# MSP430F5529_Relays_PressureSensor.net
KiCad netlist of a schematic drawn in EAGLE
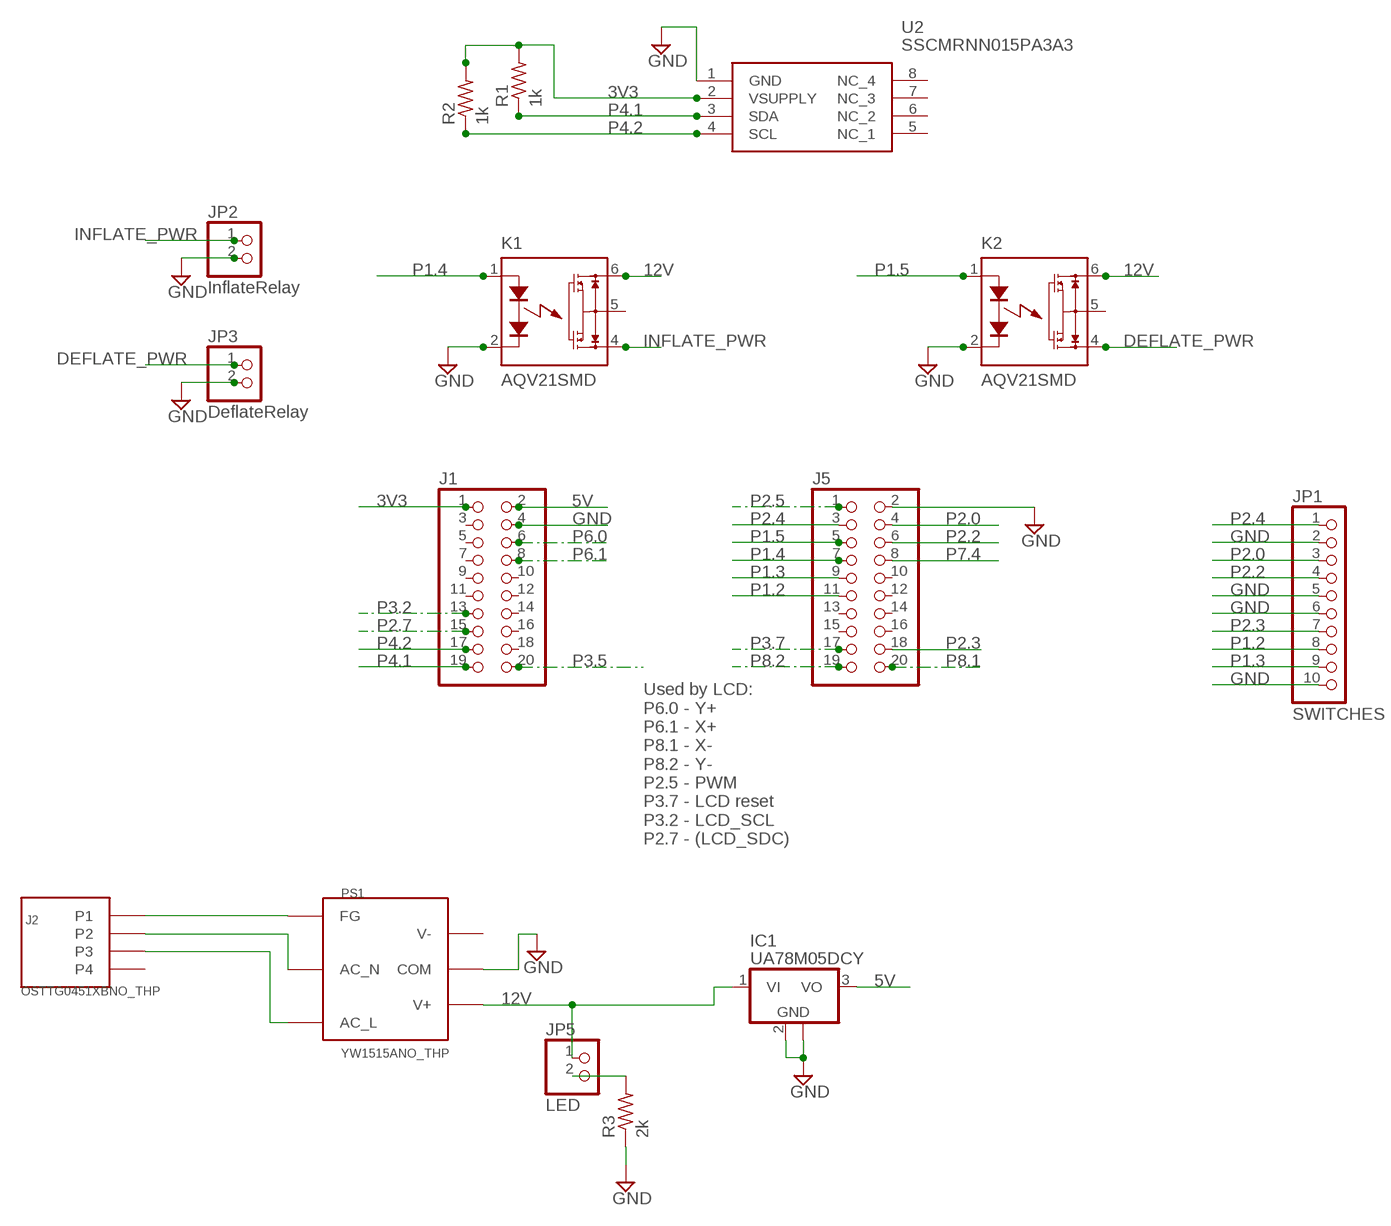
[diagram p0: schematic, sheet 1]

(export (version "E")
  (design (tool "Eeschema 10.0.6"))
  (components
    (comp (ref "IC1")
      (value "UA78M05DCY")
      (footprint "eagle-import:SOT223")
      (libsource (lib "eagle-import") (part "UA78MDCY05"))
    )
    (comp (ref "J1")
      (value "PINHD-2X10")
      (footprint "eagle-import:2X10")
      (libsource (lib "eagle-import") (part "PINHD-2X10"))
    )
    (comp (ref "J2")
      (value "OSTTG0451XBNO_THP")
      (footprint "eagle-import:TERM_4PIN_5.08MM_NO_THP")
      (libsource (lib "eagle-import") (part "OSTTG0451XBNO_THP"))
    )
    (comp (ref "J5")
      (value "PINHD-2X10")
      (footprint "eagle-import:2X10")
      (libsource (lib "eagle-import") (part "PINHD-2X10"))
    )
    (comp (ref "JP1")
      (value "SWITCHES")
      (footprint "eagle-import:1X10_90")
      (libsource (lib "eagle-import") (part "PINHD-1X10/90"))
    )
    (comp (ref "JP2")
      (value "InflateRelay")
      (footprint "eagle-import:1X02_90")
      (libsource (lib "eagle-import") (part "PINHD-1X2/90"))
    )
    (comp (ref "JP3")
      (value "DeflateRelay")
      (footprint "eagle-import:1X02_90")
      (libsource (lib "eagle-import") (part "PINHD-1X2/90"))
    )
    (comp (ref "JP5")
      (value "LED")
      (footprint "eagle-import:1X02_90")
      (libsource (lib "eagle-import") (part "PINHD-1X2/90"))
    )
    (comp (ref "K1")
      (value "AQV21SMD")
      (footprint "eagle-import:DIL06SMD")
      (fields (field (name "MF") "AROMAT/ MATSUSHITA") (field (name "MPN") "AQV210S"))
      (libsource (lib "eagle-import") (part "AQVSMD21"))
    )
    (comp (ref "K2")
      (value "AQV21SMD")
      (footprint "eagle-import:DIL06SMD")
      (fields (field (name "MF") "AROMAT/ MATSUSHITA") (field (name "MPN") "AQV210S"))
      (libsource (lib "eagle-import") (part "AQVSMD21"))
    )
    (comp (ref "PS1")
      (value "YW1515ANO_THP")
      (footprint "eagle-import:YW15_NO_THP")
      (libsource (lib "eagle-import") (part "YW1515ANO_THP"))
    )
    (comp (ref "R1")
      (value "1k")
      (footprint "eagle-import:M1206")
      (libsource (lib "eagle-import") (part "R-US_M1206"))
    )
    (comp (ref "R2")
      (value "1k")
      (footprint "eagle-import:M1206")
      (libsource (lib "eagle-import") (part "R-US_M1206"))
    )
    (comp (ref "R3")
      (value "2k")
      (footprint "eagle-import:M1206")
      (libsource (lib "eagle-import") (part "R-US_M1206"))
    )
    (comp (ref "U2")
      (value "SSCMRNN015PA3A3")
      (footprint "eagle-import:SOP254P1330X598-8N")
      (libsource (lib "eagle-import") (part "SSCMRNN015PA3A3"))
    )
  )
  (nets
    (net (code "1") (name "/3V3") (class "Default")
      (node (ref "J1") (pin "1") (pinfunction "1_1") (pintype "passive"))
      (node (ref "R1") (pin "2") (pinfunction "2_2") (pintype "passive"))
      (node (ref "R2") (pin "2") (pinfunction "2_2") (pintype "passive"))
      (node (ref "U2") (pin "2") (pinfunction "VSUPPLY_2") (pintype "power_in"))
    )
    (net (code "2") (name "/5V") (class "Default")
      (node (ref "IC1") (pin "3") (pinfunction "VO_3") (pintype "passive"))
      (node (ref "J1") (pin "2") (pinfunction "2_2") (pintype "passive"))
    )
    (net (code "3") (name "/12V") (class "Default")
      (node (ref "IC1") (pin "1") (pinfunction "VI_1") (pintype "input"))
      (node (ref "JP5") (pin "1") (pinfunction "1_1") (pintype "passive"))
      (node (ref "K1") (pin "6") (pinfunction "D1_6") (pintype "passive"))
      (node (ref "K2") (pin "6") (pinfunction "D1_6") (pintype "passive"))
      (node (ref "PS1") (pin "P4") (pinfunction "V+_P4") (pintype "power_in"))
    )
    (net (code "4") (name "/DEFLATE_PWR") (class "Default")
      (node (ref "JP3") (pin "1") (pinfunction "1_1") (pintype "passive"))
      (node (ref "K2") (pin "4") (pinfunction "D2_4") (pintype "passive"))
    )
    (net (code "5") (name "/INFLATE_PWR") (class "Default")
      (node (ref "JP2") (pin "1") (pinfunction "1_1") (pintype "passive"))
      (node (ref "K1") (pin "4") (pinfunction "D2_4") (pintype "passive"))
    )
    (net (code "6") (name "/P1.2") (class "Default")
      (node (ref "J5") (pin "11") (pinfunction "11_11") (pintype "passive"))
      (node (ref "JP1") (pin "8") (pinfunction "8_8") (pintype "passive"))
    )
    (net (code "7") (name "/P1.3") (class "Default")
      (node (ref "J5") (pin "9") (pinfunction "9_9") (pintype "passive"))
      (node (ref "JP1") (pin "9") (pinfunction "9_9") (pintype "passive"))
    )
    (net (code "8") (name "/P1.4") (class "Default")
      (node (ref "J5") (pin "7") (pinfunction "7_7") (pintype "passive"))
      (node (ref "K1") (pin "1") (pinfunction "A_1") (pintype "passive"))
    )
    (net (code "9") (name "/P1.5") (class "Default")
      (node (ref "J5") (pin "5") (pinfunction "5_5") (pintype "passive"))
      (node (ref "K2") (pin "1") (pinfunction "A_1") (pintype "passive"))
    )
    (net (code "10") (name "/P2.0") (class "Default")
      (node (ref "J5") (pin "4") (pinfunction "4_4") (pintype "passive"))
      (node (ref "JP1") (pin "3") (pinfunction "3_3") (pintype "passive"))
    )
    (net (code "11") (name "/P2.2") (class "Default")
      (node (ref "J5") (pin "6") (pinfunction "6_6") (pintype "passive"))
      (node (ref "JP1") (pin "4") (pinfunction "4_4") (pintype "passive"))
    )
    (net (code "12") (name "/P2.3") (class "Default")
      (node (ref "J5") (pin "18") (pinfunction "18_18") (pintype "passive"))
      (node (ref "JP1") (pin "7") (pinfunction "7_7") (pintype "passive"))
    )
    (net (code "13") (name "/P2.4") (class "Default")
      (node (ref "J5") (pin "3") (pinfunction "3_3") (pintype "passive"))
      (node (ref "JP1") (pin "1") (pinfunction "1_1") (pintype "passive"))
    )
    (net (code "14") (name "/P2.5") (class "Default")
      (node (ref "J5") (pin "1") (pinfunction "1_1") (pintype "passive"))
    )
    (net (code "15") (name "/P2.7") (class "Default")
      (node (ref "J1") (pin "15") (pinfunction "15_15") (pintype "passive"))
    )
    (net (code "16") (name "/P3.2") (class "Default")
      (node (ref "J1") (pin "13") (pinfunction "13_13") (pintype "passive"))
    )
    (net (code "17") (name "/P3.5") (class "Default")
      (node (ref "J1") (pin "20") (pinfunction "20_20") (pintype "passive"))
    )
    (net (code "18") (name "/P3.7") (class "Default")
      (node (ref "J5") (pin "17") (pinfunction "17_17") (pintype "passive"))
    )
    (net (code "19") (name "/P4.1") (class "Default")
      (node (ref "J1") (pin "19") (pinfunction "19_19") (pintype "passive"))
      (node (ref "R1") (pin "1") (pinfunction "1_1") (pintype "passive"))
      (node (ref "U2") (pin "3") (pinfunction "SDA_3") (pintype "bidirectional"))
    )
    (net (code "20") (name "/P4.2") (class "Default")
      (node (ref "J1") (pin "17") (pinfunction "17_17") (pintype "passive"))
      (node (ref "R2") (pin "1") (pinfunction "1_1") (pintype "passive"))
      (node (ref "U2") (pin "4") (pinfunction "SCL_4") (pintype "bidirectional"))
    )
    (net (code "21") (name "/P6.0") (class "Default")
      (node (ref "J1") (pin "6") (pinfunction "6_6") (pintype "passive"))
    )
    (net (code "22") (name "/P6.1") (class "Default")
      (node (ref "J1") (pin "8") (pinfunction "8_8") (pintype "passive"))
    )
    (net (code "23") (name "/P7.4") (class "Default")
      (node (ref "J5") (pin "8") (pinfunction "8_8") (pintype "passive"))
    )
    (net (code "24") (name "/P8.1") (class "Default")
      (node (ref "J5") (pin "20") (pinfunction "20_20") (pintype "passive"))
    )
    (net (code "25") (name "/P8.2") (class "Default")
      (node (ref "J5") (pin "19") (pinfunction "19_19") (pintype "passive"))
    )
    (net (code "26") (name "/V-") (class "Default")
      (node (ref "PS1") (pin "P6") (pinfunction "V-_P6") (pintype "power_in"))
    )
    (net (code "27") (name "GND") (class "Default")
      (node (ref "IC1") (pin "2") (pinfunction "GND_2") (pintype "passive"))
      (node (ref "IC1") (pin "4") (pinfunction "GND_4") (pintype "passive"))
      (node (ref "J1") (pin "4") (pinfunction "4_4") (pintype "passive"))
      (node (ref "J5") (pin "2") (pinfunction "2_2") (pintype "passive"))
      (node (ref "JP1") (pin "10") (pinfunction "10_10") (pintype "passive"))
      (node (ref "JP1") (pin "2") (pinfunction "2_2") (pintype "passive"))
      (node (ref "JP1") (pin "5") (pinfunction "5_5") (pintype "passive"))
      (node (ref "JP1") (pin "6") (pinfunction "6_6") (pintype "passive"))
      (node (ref "JP2") (pin "2") (pinfunction "2_2") (pintype "passive"))
      (node (ref "JP3") (pin "2") (pinfunction "2_2") (pintype "passive"))
      (node (ref "K1") (pin "2") (pinfunction "K_2") (pintype "passive"))
      (node (ref "K2") (pin "2") (pinfunction "K_2") (pintype "passive"))
      (node (ref "PS1") (pin "P5") (pinfunction "COM_P5") (pintype "power_in"))
      (node (ref "R3") (pin "1") (pinfunction "1_1") (pintype "passive"))
      (node (ref "U2") (pin "1") (pinfunction "GND_1") (pintype "power_in"))
    )
    (net (code "28") (name "Net-(JP5-Pad2)") (class "Default")
      (node (ref "JP5") (pin "2") (pinfunction "2_2") (pintype "passive"))
      (node (ref "R3") (pin "2") (pinfunction "2_2") (pintype "passive"))
    )
    (net (code "29") (name "Net-(PS1-AC_L)") (class "Default")
      (node (ref "J2") (pin "P3") (pinfunction "P3_P3") (pintype "bidirectional"))
      (node (ref "PS1") (pin "P3") (pinfunction "AC_L_P3") (pintype "power_in"))
    )
    (net (code "30") (name "Net-(PS1-AC_N)") (class "Default")
      (node (ref "J2") (pin "P2") (pinfunction "P2_P2") (pintype "bidirectional"))
      (node (ref "PS1") (pin "P2") (pinfunction "AC_N_P2") (pintype "power_in"))
    )
    (net (code "31") (name "Net-(PS1-FG)") (class "Default")
      (node (ref "J2") (pin "P1") (pinfunction "P1_P1") (pintype "bidirectional"))
      (node (ref "PS1") (pin "P1") (pinfunction "FG_P1") (pintype "power_in"))
    )
    (net (code "32") (name "unconnected-(J1-Pad3)") (class "Default")
      (node (ref "J1") (pin "3") (pinfunction "3_3") (pintype "passive"))
    )
    (net (code "33") (name "unconnected-(J1-Pad5)") (class "Default")
      (node (ref "J1") (pin "5") (pinfunction "5_5") (pintype "passive"))
    )
    (net (code "34") (name "unconnected-(J1-Pad7)") (class "Default")
      (node (ref "J1") (pin "7") (pinfunction "7_7") (pintype "passive"))
    )
    (net (code "35") (name "unconnected-(J1-Pad9)") (class "Default")
      (node (ref "J1") (pin "9") (pinfunction "9_9") (pintype "passive"))
    )
    (net (code "36") (name "unconnected-(J1-Pad10)") (class "Default")
      (node (ref "J1") (pin "10") (pinfunction "10_10") (pintype "passive"))
    )
    (net (code "37") (name "unconnected-(J1-Pad11)") (class "Default")
      (node (ref "J1") (pin "11") (pinfunction "11_11") (pintype "passive"))
    )
    (net (code "38") (name "unconnected-(J1-Pad12)") (class "Default")
      (node (ref "J1") (pin "12") (pinfunction "12_12") (pintype "passive"))
    )
    (net (code "39") (name "unconnected-(J1-Pad14)") (class "Default")
      (node (ref "J1") (pin "14") (pinfunction "14_14") (pintype "passive"))
    )
    (net (code "40") (name "unconnected-(J1-Pad16)") (class "Default")
      (node (ref "J1") (pin "16") (pinfunction "16_16") (pintype "passive"))
    )
    (net (code "41") (name "unconnected-(J1-Pad18)") (class "Default")
      (node (ref "J1") (pin "18") (pinfunction "18_18") (pintype "passive"))
    )
    (net (code "42") (name "unconnected-(J2-PadP4)") (class "Default")
      (node (ref "J2") (pin "P4") (pinfunction "P4_P4") (pintype "bidirectional"))
    )
    (net (code "43") (name "unconnected-(J5-Pad10)") (class "Default")
      (node (ref "J5") (pin "10") (pinfunction "10_10") (pintype "passive"))
    )
    (net (code "44") (name "unconnected-(J5-Pad12)") (class "Default")
      (node (ref "J5") (pin "12") (pinfunction "12_12") (pintype "passive"))
    )
    (net (code "45") (name "unconnected-(J5-Pad13)") (class "Default")
      (node (ref "J5") (pin "13") (pinfunction "13_13") (pintype "passive"))
    )
    (net (code "46") (name "unconnected-(J5-Pad14)") (class "Default")
      (node (ref "J5") (pin "14") (pinfunction "14_14") (pintype "passive"))
    )
    (net (code "47") (name "unconnected-(J5-Pad15)") (class "Default")
      (node (ref "J5") (pin "15") (pinfunction "15_15") (pintype "passive"))
    )
    (net (code "48") (name "unconnected-(J5-Pad16)") (class "Default")
      (node (ref "J5") (pin "16") (pinfunction "16_16") (pintype "passive"))
    )
    (net (code "49") (name "unconnected-(K1-S-Pad5)") (class "Default")
      (node (ref "K1") (pin "5") (pinfunction "S_5") (pintype "passive"))
    )
    (net (code "50") (name "unconnected-(K2-S-Pad5)") (class "Default")
      (node (ref "K2") (pin "5") (pinfunction "S_5") (pintype "passive"))
    )
    (net (code "51") (name "unconnected-(U2-NC_1-Pad5)") (class "Default")
      (node (ref "U2") (pin "5") (pinfunction "NC_1_5") (pintype "bidirectional"))
    )
    (net (code "52") (name "unconnected-(U2-NC_2-Pad6)") (class "Default")
      (node (ref "U2") (pin "6") (pinfunction "NC_2_6") (pintype "bidirectional"))
    )
    (net (code "53") (name "unconnected-(U2-NC_3-Pad7)") (class "Default")
      (node (ref "U2") (pin "7") (pinfunction "NC_3_7") (pintype "bidirectional"))
    )
    (net (code "54") (name "unconnected-(U2-NC_4-Pad8)") (class "Default")
      (node (ref "U2") (pin "8") (pinfunction "NC_4_8") (pintype "bidirectional"))
    )
  )
)
